# Ilham_Widyo_Nugroho_21507334002_1.net
KiCad netlist of a schematic drawn in EAGLE
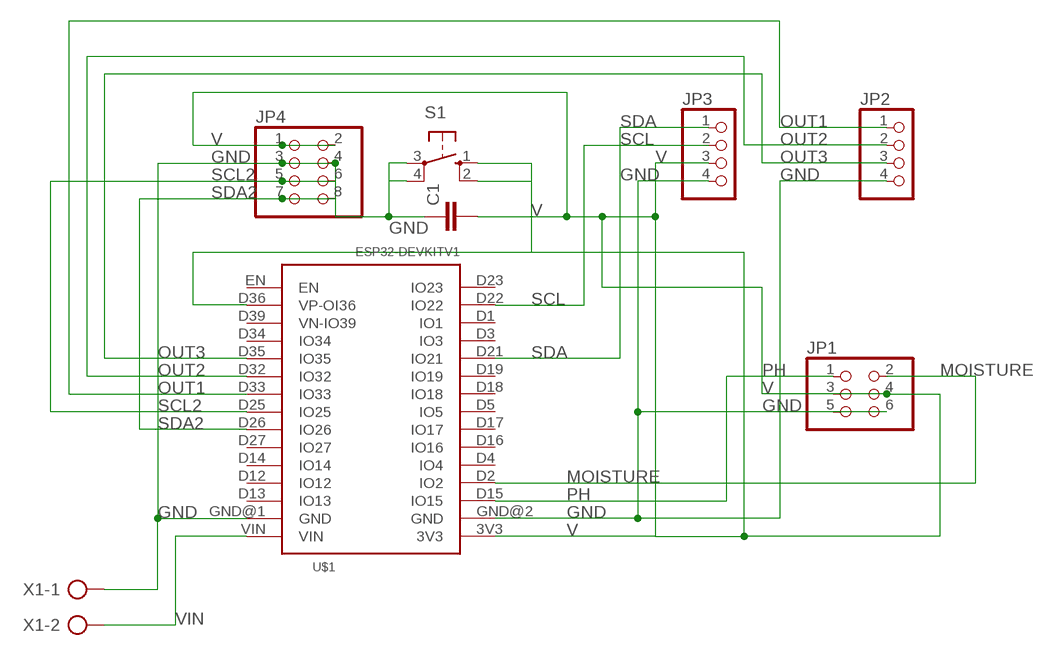
[diagram p0: schematic, sheet 1]

(export (version "E")
  (design (tool "Eeschema 10.0.6"))
  (components
    (comp (ref "C1")
      (value "C-EU050-030X075")
      (footprint "eagle-import:C050-030X075")
      (libsource (lib "eagle-import") (part "C-EU050-030X075"))
    )
    (comp (ref "JP1")
      (value "PINHD-2X3")
      (footprint "eagle-import:2X03")
      (libsource (lib "eagle-import") (part "PINHD-2X3"))
    )
    (comp (ref "JP2")
      (value "PINHD-1X4")
      (footprint "eagle-import:1X04")
      (libsource (lib "eagle-import") (part "PINHD-1X4"))
    )
    (comp (ref "JP3")
      (value "PINHD-1X4")
      (footprint "eagle-import:1X04")
      (libsource (lib "eagle-import") (part "PINHD-1X4"))
    )
    (comp (ref "JP4")
      (value "PINHD-2X4")
      (footprint "eagle-import:2X04")
      (libsource (lib "eagle-import") (part "PINHD-2X4"))
    )
    (comp (ref "S1")
      (value "10-XX")
      (footprint "eagle-import:B3F-10XX")
      (fields (field (name "MPN") "B3F-1000"))
      (libsource (lib "eagle-import") (part "10-XX"))
    )
    (comp (ref "U$1")
      (value "ESP32DEVKITV1")
      (footprint "eagle-import:ESP32-DEVKITV1")
      (libsource (lib "eagle-import") (part "ESP32DEVKITV1"))
    )
    (comp (ref "X1")
      (value "AK300/2")
      (footprint "eagle-import:AK300_2")
      (libsource (lib "eagle-import") (part "AK300/2"))
    )
  )
  (nets
    (net (code "1") (name "/GND") (class "Default")
      (node (ref "C1") (pin "1") (pinfunction "1_1") (pintype "passive"))
      (node (ref "JP1") (pin "5") (pinfunction "5_5") (pintype "passive"))
      (node (ref "JP1") (pin "6") (pinfunction "6_6") (pintype "passive"))
      (node (ref "JP2") (pin "4") (pinfunction "4_4") (pintype "passive"))
      (node (ref "JP3") (pin "4") (pinfunction "4_4") (pintype "passive"))
      (node (ref "JP4") (pin "3") (pinfunction "3_3") (pintype "passive"))
      (node (ref "JP4") (pin "4") (pinfunction "4_4") (pintype "passive"))
      (node (ref "S1") (pin "3") (pinfunction "P_3") (pintype "passive"))
      (node (ref "S1") (pin "4") (pinfunction "P1_4") (pintype "passive"))
      (node (ref "U$1") (pin "GND@1") (pinfunction "GND_GND@1") (pintype "bidirectional"))
      (node (ref "U$1") (pin "GND@2") (pinfunction "GND_GND@2") (pintype "bidirectional"))
      (node (ref "X1") (pin "1") (pinfunction "KL_1") (pintype "passive"))
    )
    (net (code "2") (name "/MOISTURE") (class "Default")
      (node (ref "JP1") (pin "2") (pinfunction "2_2") (pintype "passive"))
      (node (ref "U$1") (pin "D2") (pinfunction "IO2_D2") (pintype "bidirectional"))
    )
    (net (code "3") (name "/OUT1") (class "Default")
      (node (ref "JP2") (pin "1") (pinfunction "1_1") (pintype "passive"))
      (node (ref "U$1") (pin "D33") (pinfunction "IO33_D33") (pintype "bidirectional"))
    )
    (net (code "4") (name "/OUT2") (class "Default")
      (node (ref "JP2") (pin "2") (pinfunction "2_2") (pintype "passive"))
      (node (ref "U$1") (pin "D32") (pinfunction "IO32_D32") (pintype "bidirectional"))
    )
    (net (code "5") (name "/OUT3") (class "Default")
      (node (ref "JP2") (pin "3") (pinfunction "3_3") (pintype "passive"))
      (node (ref "U$1") (pin "D35") (pinfunction "IO35_D35") (pintype "bidirectional"))
    )
    (net (code "6") (name "/PH") (class "Default")
      (node (ref "JP1") (pin "1") (pinfunction "1_1") (pintype "passive"))
      (node (ref "U$1") (pin "D15") (pinfunction "IO15_D15") (pintype "bidirectional"))
    )
    (net (code "7") (name "/SCL") (class "Default")
      (node (ref "JP3") (pin "2") (pinfunction "2_2") (pintype "passive"))
      (node (ref "U$1") (pin "D22") (pinfunction "IO22_D22") (pintype "bidirectional"))
    )
    (net (code "8") (name "/SCL2") (class "Default")
      (node (ref "JP4") (pin "5") (pinfunction "5_5") (pintype "passive"))
      (node (ref "JP4") (pin "6") (pinfunction "6_6") (pintype "passive"))
      (node (ref "U$1") (pin "D25") (pinfunction "IO25_D25") (pintype "bidirectional"))
    )
    (net (code "9") (name "/SDA") (class "Default")
      (node (ref "JP3") (pin "1") (pinfunction "1_1") (pintype "passive"))
      (node (ref "U$1") (pin "D21") (pinfunction "IO21_D21") (pintype "bidirectional"))
    )
    (net (code "10") (name "/SDA2") (class "Default")
      (node (ref "JP4") (pin "7") (pinfunction "7_7") (pintype "passive"))
      (node (ref "JP4") (pin "8") (pinfunction "8_8") (pintype "passive"))
      (node (ref "U$1") (pin "D26") (pinfunction "IO26_D26") (pintype "bidirectional"))
    )
    (net (code "11") (name "/V") (class "Default")
      (node (ref "C1") (pin "2") (pinfunction "2_2") (pintype "passive"))
      (node (ref "JP1") (pin "3") (pinfunction "3_3") (pintype "passive"))
      (node (ref "JP1") (pin "4") (pinfunction "4_4") (pintype "passive"))
      (node (ref "JP3") (pin "3") (pinfunction "3_3") (pintype "passive"))
      (node (ref "JP4") (pin "1") (pinfunction "1_1") (pintype "passive"))
      (node (ref "JP4") (pin "2") (pinfunction "2_2") (pintype "passive"))
      (node (ref "S1") (pin "1") (pinfunction "S_1") (pintype "passive"))
      (node (ref "S1") (pin "2") (pinfunction "S1_2") (pintype "passive"))
      (node (ref "U$1") (pin "3V3") (pinfunction "3V3_3V3") (pintype "bidirectional"))
      (node (ref "U$1") (pin "D36") (pinfunction "VP-OI36_D36") (pintype "bidirectional"))
    )
    (net (code "12") (name "/VIN") (class "Default")
      (node (ref "U$1") (pin "VIN") (pinfunction "VIN_VIN") (pintype "bidirectional"))
      (node (ref "X1") (pin "2") (pinfunction "KL_2") (pintype "passive"))
    )
    (net (code "13") (name "unconnected-(U$1-IO1-PadD1)") (class "Default")
      (node (ref "U$1") (pin "D1") (pinfunction "IO1_D1") (pintype "bidirectional"))
    )
    (net (code "14") (name "unconnected-(U$1-IO3-PadD3)") (class "Default")
      (node (ref "U$1") (pin "D3") (pinfunction "IO3_D3") (pintype "bidirectional"))
    )
    (net (code "15") (name "unconnected-(U$1-IO4-PadD4)") (class "Default")
      (node (ref "U$1") (pin "D4") (pinfunction "IO4_D4") (pintype "bidirectional"))
    )
    (net (code "16") (name "unconnected-(U$1-IO5-PadD5)") (class "Default")
      (node (ref "U$1") (pin "D5") (pinfunction "IO5_D5") (pintype "bidirectional"))
    )
    (net (code "17") (name "unconnected-(U$1-IO12-PadD12)") (class "Default")
      (node (ref "U$1") (pin "D12") (pinfunction "IO12_D12") (pintype "bidirectional"))
    )
    (net (code "18") (name "unconnected-(U$1-IO13-PadD13)") (class "Default")
      (node (ref "U$1") (pin "D13") (pinfunction "IO13_D13") (pintype "bidirectional"))
    )
    (net (code "19") (name "unconnected-(U$1-IO14-PadD14)") (class "Default")
      (node (ref "U$1") (pin "D14") (pinfunction "IO14_D14") (pintype "bidirectional"))
    )
    (net (code "20") (name "unconnected-(U$1-IO16-PadD16)") (class "Default")
      (node (ref "U$1") (pin "D16") (pinfunction "IO16_D16") (pintype "bidirectional"))
    )
    (net (code "21") (name "unconnected-(U$1-IO17-PadD17)") (class "Default")
      (node (ref "U$1") (pin "D17") (pinfunction "IO17_D17") (pintype "bidirectional"))
    )
    (net (code "22") (name "unconnected-(U$1-IO18-PadD18)") (class "Default")
      (node (ref "U$1") (pin "D18") (pinfunction "IO18_D18") (pintype "bidirectional"))
    )
    (net (code "23") (name "unconnected-(U$1-IO19-PadD19)") (class "Default")
      (node (ref "U$1") (pin "D19") (pinfunction "IO19_D19") (pintype "bidirectional"))
    )
    (net (code "24") (name "unconnected-(U$1-IO23-PadD23)") (class "Default")
      (node (ref "U$1") (pin "D23") (pinfunction "IO23_D23") (pintype "bidirectional"))
    )
    (net (code "25") (name "unconnected-(U$1-IO27-PadD27)") (class "Default")
      (node (ref "U$1") (pin "D27") (pinfunction "IO27_D27") (pintype "bidirectional"))
    )
    (net (code "26") (name "unconnected-(U$1-IO34-PadD34)") (class "Default")
      (node (ref "U$1") (pin "D34") (pinfunction "IO34_D34") (pintype "bidirectional"))
    )
    (net (code "27") (name "unconnected-(U$1-PadEN)") (class "Default")
      (node (ref "U$1") (pin "EN") (pinfunction "EN_EN") (pintype "bidirectional"))
    )
    (net (code "28") (name "unconnected-(U$1-VN-IO39-PadD39)") (class "Default")
      (node (ref "U$1") (pin "D39") (pinfunction "VN-IO39_D39") (pintype "bidirectional"))
    )
  )
)
